# SHEET1.net
KiCad netlist of a schematic drawn in Altium Designer
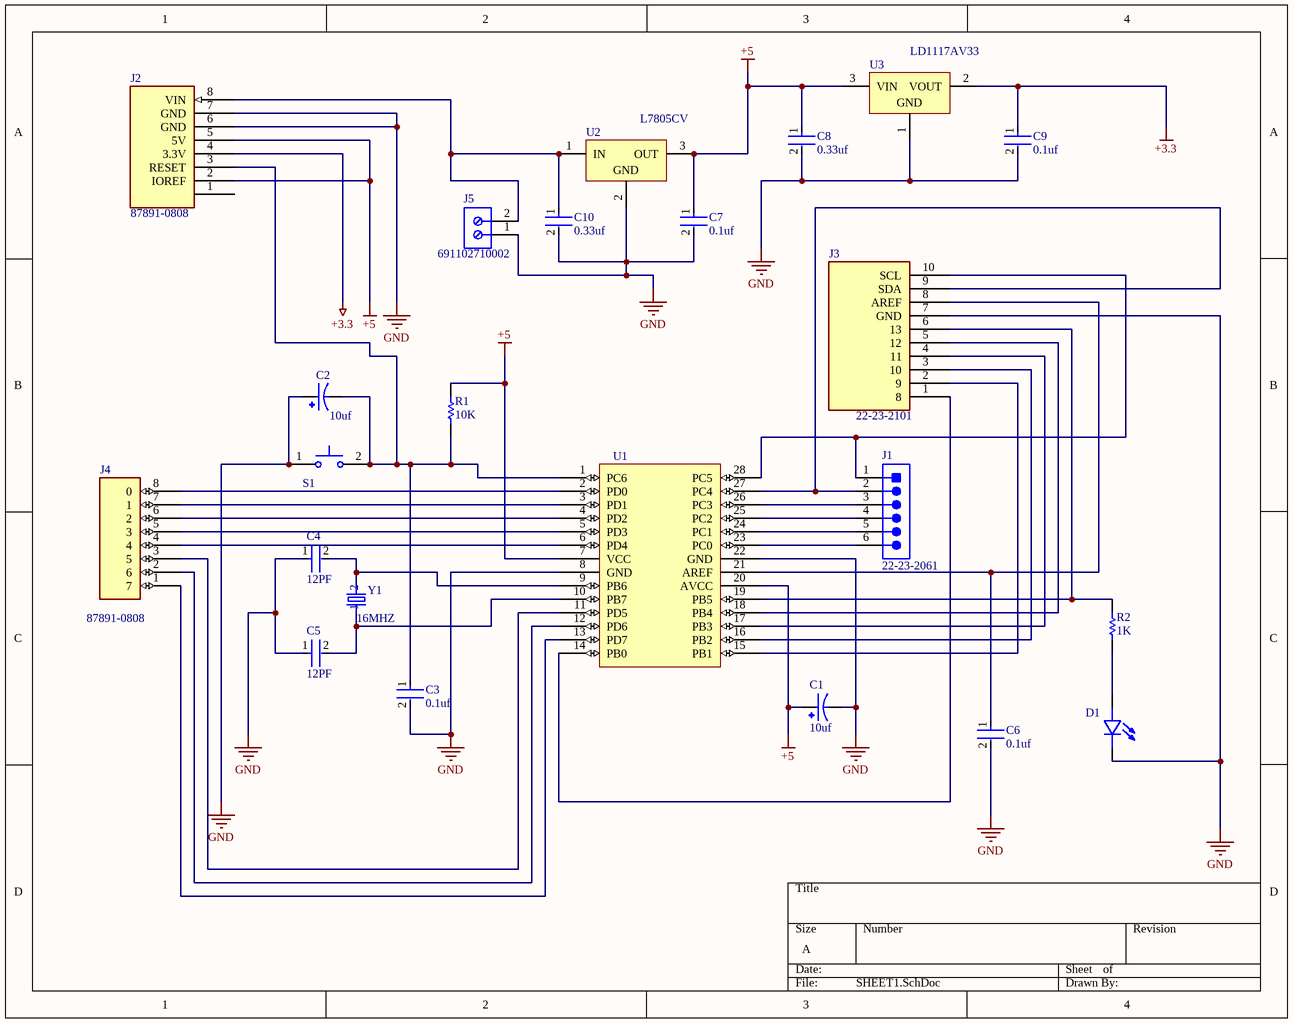
[diagram p0: SHEET1.SchDoc]

(export (version "E")
  (design (tool "Eeschema 10.0.6"))
  (components
    (comp (ref "C1")
      (value "10uf")
      (footprint "PcbLib1:CAPPRD500W50D630H1120")
      (description "Cap Aluminum Lytic 10uF 100V 20% Radial 105C Automotive Ammo")
      (fields (field (name "MF") "Panasonic") (field (name "MP") "EEU-FC2A100B"))
      (libsource (lib "*") (part "EEUFC2A100B"))
    )
    (comp (ref "C2")
      (value "10uf")
      (footprint "PcbLib1:CAPPRD500W50D630H1120")
      (description "Cap Aluminum Lytic 10uF 100V 20% Radial 105C Automotive Ammo")
      (fields (field (name "MF") "Panasonic") (field (name "MP") "EEU-FC2A100B"))
      (libsource (lib "*") (part "EEUFC2A100B"))
    )
    (comp (ref "C3")
      (value "0.1uf")
      (footprint "FP-K15H5-MFG")
      (description "CAP CER 0.1UF 50V X7R RADIAL")
      (fields (field (name "TOLERANCE") "10%") (field (name "VOLTAGE") "50V"))
      (libsource (lib "Altium Content Vault") (part "02cd4be3c70576c341d710602a673aa"))
    )
    (comp (ref "C4")
      (value "12PF")
      (footprint "FP-K15H5-MFG")
      (description "CAP CER 0.1UF 50V X7R RADIAL")
      (fields (field (name "TOLERANCE") "10%") (field (name "VOLTAGE") "50V"))
      (libsource (lib "Altium Content Vault") (part "02cd4be3c70576c341d710602a673aa"))
    )
    (comp (ref "C5")
      (value "12PF")
      (footprint "FP-K15H5-MFG")
      (description "CAP CER 0.1UF 50V X7R RADIAL")
      (fields (field (name "TOLERANCE") "10%") (field (name "VOLTAGE") "50V"))
      (libsource (lib "Altium Content Vault") (part "02cd4be3c70576c341d710602a673aa"))
    )
    (comp (ref "C6")
      (value "0.1uf")
      (footprint "FP-K15H5-MFG")
      (description "CAP CER 0.1UF 50V X7R RADIAL")
      (fields (field (name "TOLERANCE") "10%") (field (name "VOLTAGE") "50V"))
      (libsource (lib "Altium Content Vault") (part "02cd4be3c70576c341d710602a673aa"))
    )
    (comp (ref "C7")
      (value "0.1uf")
      (footprint "FP-K15H5-MFG")
      (description "CAP CER 0.1UF 50V X7R RADIAL")
      (fields (field (name "TOLERANCE") "10%") (field (name "VOLTAGE") "50V"))
      (libsource (lib "Altium Content Vault") (part "02cd4be3c70576c341d710602a673aa"))
    )
    (comp (ref "C8")
      (value "0.33uf")
      (footprint "FP-K15H5-MFG")
      (description "CAP CER 0.1UF 50V X7R RADIAL")
      (fields (field (name "TOLERANCE") "10%") (field (name "VOLTAGE") "50V"))
      (libsource (lib "Altium Content Vault") (part "02cd4be3c70576c341d710602a673aa"))
    )
    (comp (ref "C9")
      (value "0.1uf")
      (footprint "FP-K15H5-MFG")
      (description "CAP CER 0.1UF 50V X7R RADIAL")
      (fields (field (name "TOLERANCE") "10%") (field (name "VOLTAGE") "50V"))
      (libsource (lib "Altium Content Vault") (part "02cd4be3c70576c341d710602a673aa"))
    )
    (comp (ref "C10")
      (value "0.33uf")
      (footprint "FP-K15H5-MFG")
      (description "CAP CER 0.1UF 50V X7R RADIAL")
      (fields (field (name "TOLERANCE") "10%") (field (name "VOLTAGE") "50V"))
      (libsource (lib "Altium Content Vault") (part "02cd4be3c70576c341d710602a673aa"))
    )
    (comp (ref "D1")
      (value "~")
      (footprint "LED_WP7113LGD")
      (description "LED 5mm Round Yellow 30 deg. ¦ Optek (TT Electronics) OVLFY3C7")
      (fields (field (name "MF") "TT Electronics/Optek Technology") (field (name "MP") "OVLFY3C7"))
      (libsource (lib "*") (part "OVLFY3C7"))
    )
    (comp (ref "J1")
      (value "22-23-2061")
      (footprint "MOLX-22-23-2061_V")
      (fields (field (name "MANUFACTURER") "Molex"))
      (libsource (lib "Altium Content Vault") (part "CN-1P-M-R6"))
    )
    (comp (ref "J2")
      (value "87891-0808")
      (footprint "HDRV8W69P0X254_1X8_2032X251X1641P")
      (description "Headers & Wire Housings 2.54MM PITCH SRSW T/H HEADER 8 CKT")
      (fields (field (name "MOUSER PART NUMBER") "538-87891-0808"))
      (libsource (lib "*") (part "87891-0808"))
    )
    (comp (ref "J3")
      (value "22-23-2101")
      (footprint "SHDR10W87P0X254_1X10_2525X635X1105P")
      (fields (field (name "MOUSER PART NUMBER") "538-22-23-2101"))
      (libsource (lib "*") (part "22-23-2101"))
    )
    (comp (ref "J4")
      (value "87891-0808")
      (footprint "HDRV8W69P0X254_1X8_2032X251X1641P")
      (description "Headers & Wire Housings 2.54MM PITCH SRSW T/H HEADER 8 CKT")
      (fields (field (name "MOUSER PART NUMBER") "538-87891-0808"))
      (libsource (lib "*") (part "PIN DIGITAL"))
    )
    (comp (ref "J5")
      (value "691102710002")
      (footprint "691102710002")
      (fields (field (name "VOLTAGE") "300V"))
      (libsource (lib "Altium Content Vault") (part "TBL - 1R - 02P - Screw"))
    )
    (comp (ref "R1")
      (value "10K")
      (footprint "res")
      (description "Resistor")
      (libsource (lib "Simulation Generic Components") (part "Resistor"))
    )
    (comp (ref "R2")
      (value "1K")
      (footprint "res")
      (description "Resistor")
      (libsource (lib "Simulation Generic Components") (part "Resistor"))
    )
    (comp (ref "S1")
      (value "~")
      (footprint "SW_BUTT-2")
      (description "Tactile Switches MINI PUSH BUTTON SWITCH 2-PIN QTY. 4")
      (fields (field (name "MF") "Gravitech") (field (name "MP") "BUTT-2"))
      (libsource (lib "*") (part "BUTT-2"))
    )
    (comp (ref "U1")
      (value "~")
      (footprint "DIP787W46P254L3467H508Q28")
      (libsource (lib "*") (part "atmega328p"))
    )
    (comp (ref "U2")
      (value "L7805CV")
      (footprint "TO220")
      (description "Positive Voltage Regulator, 5V, 3-Pin TO-220")
      (libsource (lib "Altium Content Vault") (part "PM-REG-L4940-SIL3"))
    )
    (comp (ref "U3")
      (value "LD1117AV33")
      (footprint "TO220")
      (description "1A, Low Drop Positive Voltage Regulator, 3.3V, 3-Pin TO-220")
      (libsource (lib "Altium Content Vault") (part "PM-REG-LD1117V-SIL3"))
    )
    (comp (ref "Y1")
      (value "16MHZ")
      (footprint "XT9S20ANA16M")
      (description "Microprocessor, Crystal; 16 MHz; + 30 ppm _Typ._ @ 25 degC; 7 pF _Max._; 40 Ohm")
      (fields (field (name "MF") "Vishay Dale") (field (name "MP") "XT9S20ANA16M"))
      (libsource (lib "*") (part "XT9S20ANA16M"))
    )
  )
  (nets
    (net (code "1") (name "+3.3") (class "Default")
      (node (ref "C9") (pin "1") (pinfunction "1_1") (pintype "passive"))
      (node (ref "J2") (pin "4") (pinfunction "3.3V_4") (pintype "power_in"))
      (node (ref "U3") (pin "2") (pinfunction "VOUT_2") (pintype "power_in"))
    )
    (net (code "2") (name "+5") (class "Default")
      (node (ref "C1") (pin "P") (pinfunction "P_P") (pintype "passive"))
      (node (ref "C7") (pin "1") (pinfunction "1_1") (pintype "passive"))
      (node (ref "C8") (pin "1") (pinfunction "1_1") (pintype "passive"))
      (node (ref "J2") (pin "2") (pinfunction "IOREF_2") (pintype "power_in"))
      (node (ref "J2") (pin "5") (pinfunction "5V_5") (pintype "power_in"))
      (node (ref "R1") (pin "2") (pinfunction "2_2") (pintype "passive"))
      (node (ref "U1") (pin "20") (pinfunction "AVCC_20") (pintype "power_in"))
      (node (ref "U1") (pin "7") (pinfunction "VCC_7") (pintype "power_in"))
      (node (ref "U2") (pin "3") (pinfunction "OUT_3") (pintype "power_in"))
      (node (ref "U3") (pin "3") (pinfunction "VIN_3") (pintype "power_in"))
    )
    (net (code "3") (name "GND") (class "Default")
      (node (ref "C1") (pin "N") (pinfunction "N_N") (pintype "passive"))
      (node (ref "C10") (pin "2") (pinfunction "2_2") (pintype "passive"))
      (node (ref "C2") (pin "P") (pinfunction "P_P") (pintype "passive"))
      (node (ref "C3") (pin "2") (pinfunction "2_2") (pintype "passive"))
      (node (ref "C4") (pin "1") (pinfunction "1_1") (pintype "passive"))
      (node (ref "C5") (pin "1") (pinfunction "1_1") (pintype "passive"))
      (node (ref "C6") (pin "2") (pinfunction "2_2") (pintype "passive"))
      (node (ref "C7") (pin "2") (pinfunction "2_2") (pintype "passive"))
      (node (ref "C8") (pin "2") (pinfunction "2_2") (pintype "passive"))
      (node (ref "C9") (pin "2") (pinfunction "2_2") (pintype "passive"))
      (node (ref "D1") (pin "2") (pinfunction "C_2") (pintype "passive"))
      (node (ref "J2") (pin "6") (pinfunction "GND_6") (pintype "power_in"))
      (node (ref "J2") (pin "7") (pinfunction "GND_7") (pintype "power_in"))
      (node (ref "J3") (pin "7") (pinfunction "GND_7") (pintype "passive"))
      (node (ref "J5") (pin "1") (pinfunction "1_1") (pintype "passive"))
      (node (ref "S1") (pin "1") (pinfunction "1_1") (pintype "passive"))
      (node (ref "U1") (pin "22") (pinfunction "GND_22") (pintype "power_in"))
      (node (ref "U1") (pin "8") (pinfunction "GND_8") (pintype "power_in"))
      (node (ref "U2") (pin "2") (pinfunction "GND_2") (pintype "power_in"))
      (node (ref "U3") (pin "1") (pinfunction "GND_1") (pintype "power_in"))
    )
    (net (code "4") (name "Net-(D1-A)") (class "Default")
      (node (ref "D1") (pin "1") (pinfunction "A_1") (pintype "passive"))
      (node (ref "R2") (pin "1") (pinfunction "1_1") (pintype "passive"))
    )
    (net (code "5") (name "Net-(J2-RESET)") (class "Default")
      (node (ref "C2") (pin "N") (pinfunction "N_N") (pintype "passive"))
      (node (ref "C3") (pin "1") (pinfunction "1_1") (pintype "passive"))
      (node (ref "J2") (pin "3") (pinfunction "RESET_3") (pintype "passive"))
      (node (ref "R1") (pin "1") (pinfunction "1_1") (pintype "passive"))
      (node (ref "S1") (pin "2") (pinfunction "2_2") (pintype "passive"))
      (node (ref "U1") (pin "1") (pinfunction "PC6_1") (pintype "bidirectional"))
    )
    (net (code "6") (name "Net-(J2-VIN)") (class "Default")
      (node (ref "C10") (pin "1") (pinfunction "1_1") (pintype "passive"))
      (node (ref "J2") (pin "8") (pinfunction "VIN_8") (pintype "input"))
      (node (ref "J5") (pin "2") (pinfunction "2_2") (pintype "passive"))
      (node (ref "U2") (pin "1") (pinfunction "IN_1") (pintype "power_in"))
    )
    (net (code "7") (name "Net-(J3-8)") (class "Default")
      (node (ref "J3") (pin "1") (pinfunction "8_1") (pintype "passive"))
      (node (ref "U1") (pin "14") (pinfunction "PB0_14") (pintype "bidirectional"))
    )
    (net (code "8") (name "Net-(J3-9)") (class "Default")
      (node (ref "J3") (pin "2") (pinfunction "9_2") (pintype "passive"))
      (node (ref "U1") (pin "15") (pinfunction "PB1_15") (pintype "bidirectional"))
    )
    (net (code "9") (name "Net-(J3-10)") (class "Default")
      (node (ref "J3") (pin "3") (pinfunction "10_3") (pintype "passive"))
      (node (ref "U1") (pin "16") (pinfunction "PB2_16") (pintype "bidirectional"))
    )
    (net (code "10") (name "Net-(J3-11)") (class "Default")
      (node (ref "J3") (pin "4") (pinfunction "11_4") (pintype "passive"))
      (node (ref "U1") (pin "17") (pinfunction "PB3_17") (pintype "bidirectional"))
    )
    (net (code "11") (name "Net-(J3-12)") (class "Default")
      (node (ref "J3") (pin "5") (pinfunction "12_5") (pintype "passive"))
      (node (ref "U1") (pin "18") (pinfunction "PB4_18") (pintype "bidirectional"))
    )
    (net (code "12") (name "Net-(J3-13)") (class "Default")
      (node (ref "J3") (pin "6") (pinfunction "13_6") (pintype "passive"))
      (node (ref "R2") (pin "2") (pinfunction "2_2") (pintype "passive"))
      (node (ref "U1") (pin "19") (pinfunction "PB5_19") (pintype "bidirectional"))
    )
    (net (code "13") (name "Net-(J3-AREF)") (class "Default")
      (node (ref "C6") (pin "1") (pinfunction "1_1") (pintype "passive"))
      (node (ref "J3") (pin "8") (pinfunction "AREF_8") (pintype "passive"))
      (node (ref "U1") (pin "21") (pinfunction "AREF_21") (pintype "power_in"))
    )
    (net (code "14") (name "Net-(J3-SCL)") (class "Default")
      (node (ref "J1") (pin "1") (pinfunction "1_1") (pintype "passive"))
      (node (ref "J3") (pin "10") (pinfunction "SCL_10") (pintype "passive"))
      (node (ref "U1") (pin "28") (pinfunction "PC5_28") (pintype "bidirectional"))
    )
    (net (code "15") (name "Net-(J3-SDA)") (class "Default")
      (node (ref "J1") (pin "2") (pinfunction "2_2") (pintype "passive"))
      (node (ref "J3") (pin "9") (pinfunction "SDA_9") (pintype "passive"))
      (node (ref "U1") (pin "27") (pinfunction "PC4_27") (pintype "bidirectional"))
    )
    (net (code "16") (name "Net-(J4-0)") (class "Default")
      (node (ref "J4") (pin "8") (pinfunction "0_8") (pintype "bidirectional"))
      (node (ref "U1") (pin "2") (pinfunction "PD0_2") (pintype "bidirectional"))
    )
    (net (code "17") (name "Net-(J4-1)") (class "Default")
      (node (ref "J4") (pin "7") (pinfunction "1_7") (pintype "bidirectional"))
      (node (ref "U1") (pin "3") (pinfunction "PD1_3") (pintype "bidirectional"))
    )
    (net (code "18") (name "Net-(J4-2)") (class "Default")
      (node (ref "J4") (pin "6") (pinfunction "2_6") (pintype "bidirectional"))
      (node (ref "U1") (pin "4") (pinfunction "PD2_4") (pintype "bidirectional"))
    )
    (net (code "19") (name "Net-(J4-3)") (class "Default")
      (node (ref "J4") (pin "5") (pinfunction "3_5") (pintype "bidirectional"))
      (node (ref "U1") (pin "5") (pinfunction "PD3_5") (pintype "bidirectional"))
    )
    (net (code "20") (name "Net-(J4-5)") (class "Default")
      (node (ref "J4") (pin "3") (pinfunction "5_3") (pintype "bidirectional"))
      (node (ref "U1") (pin "11") (pinfunction "PD5_11") (pintype "bidirectional"))
    )
    (net (code "21") (name "Net-(J4-6)") (class "Default")
      (node (ref "J4") (pin "2") (pinfunction "6_2") (pintype "bidirectional"))
      (node (ref "U1") (pin "12") (pinfunction "PD6_12") (pintype "bidirectional"))
    )
    (net (code "22") (name "Net-(J4-7)") (class "Default")
      (node (ref "J4") (pin "1") (pinfunction "7_1") (pintype "bidirectional"))
      (node (ref "U1") (pin "13") (pinfunction "PD7_13") (pintype "bidirectional"))
    )
    (net (code "23") (name "Net-(U1-PB6)") (class "Default")
      (node (ref "C4") (pin "2") (pinfunction "2_2") (pintype "passive"))
      (node (ref "U1") (pin "9") (pinfunction "PB6_9") (pintype "bidirectional"))
      (node (ref "Y1") (pin "2") (pinfunction "2_2") (pintype "passive"))
    )
    (net (code "24") (name "Net-(U1-PB7)") (class "Default")
      (node (ref "C5") (pin "2") (pinfunction "2_2") (pintype "passive"))
      (node (ref "U1") (pin "10") (pinfunction "PB7_10") (pintype "bidirectional"))
      (node (ref "Y1") (pin "1") (pinfunction "1_1") (pintype "passive"))
    )
    (net (code "25") (name "Net-(U1-PC0)") (class "Default")
      (node (ref "J1") (pin "6") (pinfunction "6_6") (pintype "passive"))
      (node (ref "U1") (pin "23") (pinfunction "PC0_23") (pintype "bidirectional"))
    )
    (net (code "26") (name "Net-(U1-PC1)") (class "Default")
      (node (ref "J1") (pin "5") (pinfunction "5_5") (pintype "passive"))
      (node (ref "U1") (pin "24") (pinfunction "PC1_24") (pintype "bidirectional"))
    )
    (net (code "27") (name "Net-(U1-PC2)") (class "Default")
      (node (ref "J1") (pin "4") (pinfunction "4_4") (pintype "passive"))
      (node (ref "U1") (pin "25") (pinfunction "PC2_25") (pintype "bidirectional"))
    )
    (net (code "28") (name "Net-(U1-PC3)") (class "Default")
      (node (ref "J1") (pin "3") (pinfunction "3_3") (pintype "passive"))
      (node (ref "U1") (pin "26") (pinfunction "PC3_26") (pintype "bidirectional"))
    )
    (net (code "29") (name "Net-(U1-PD4)") (class "Default")
      (node (ref "J4") (pin "4") (pinfunction "4_4") (pintype "bidirectional"))
      (node (ref "U1") (pin "6") (pinfunction "PD4_6") (pintype "bidirectional"))
    )
    (net (code "30") (name "unconnected-(J2-Pad1)") (class "Default")
      (node (ref "J2") (pin "1") (pintype "passive"))
    )
  )
)
